# Shift_Regs.net
KiCad netlist of a schematic drawn in Altium Designer
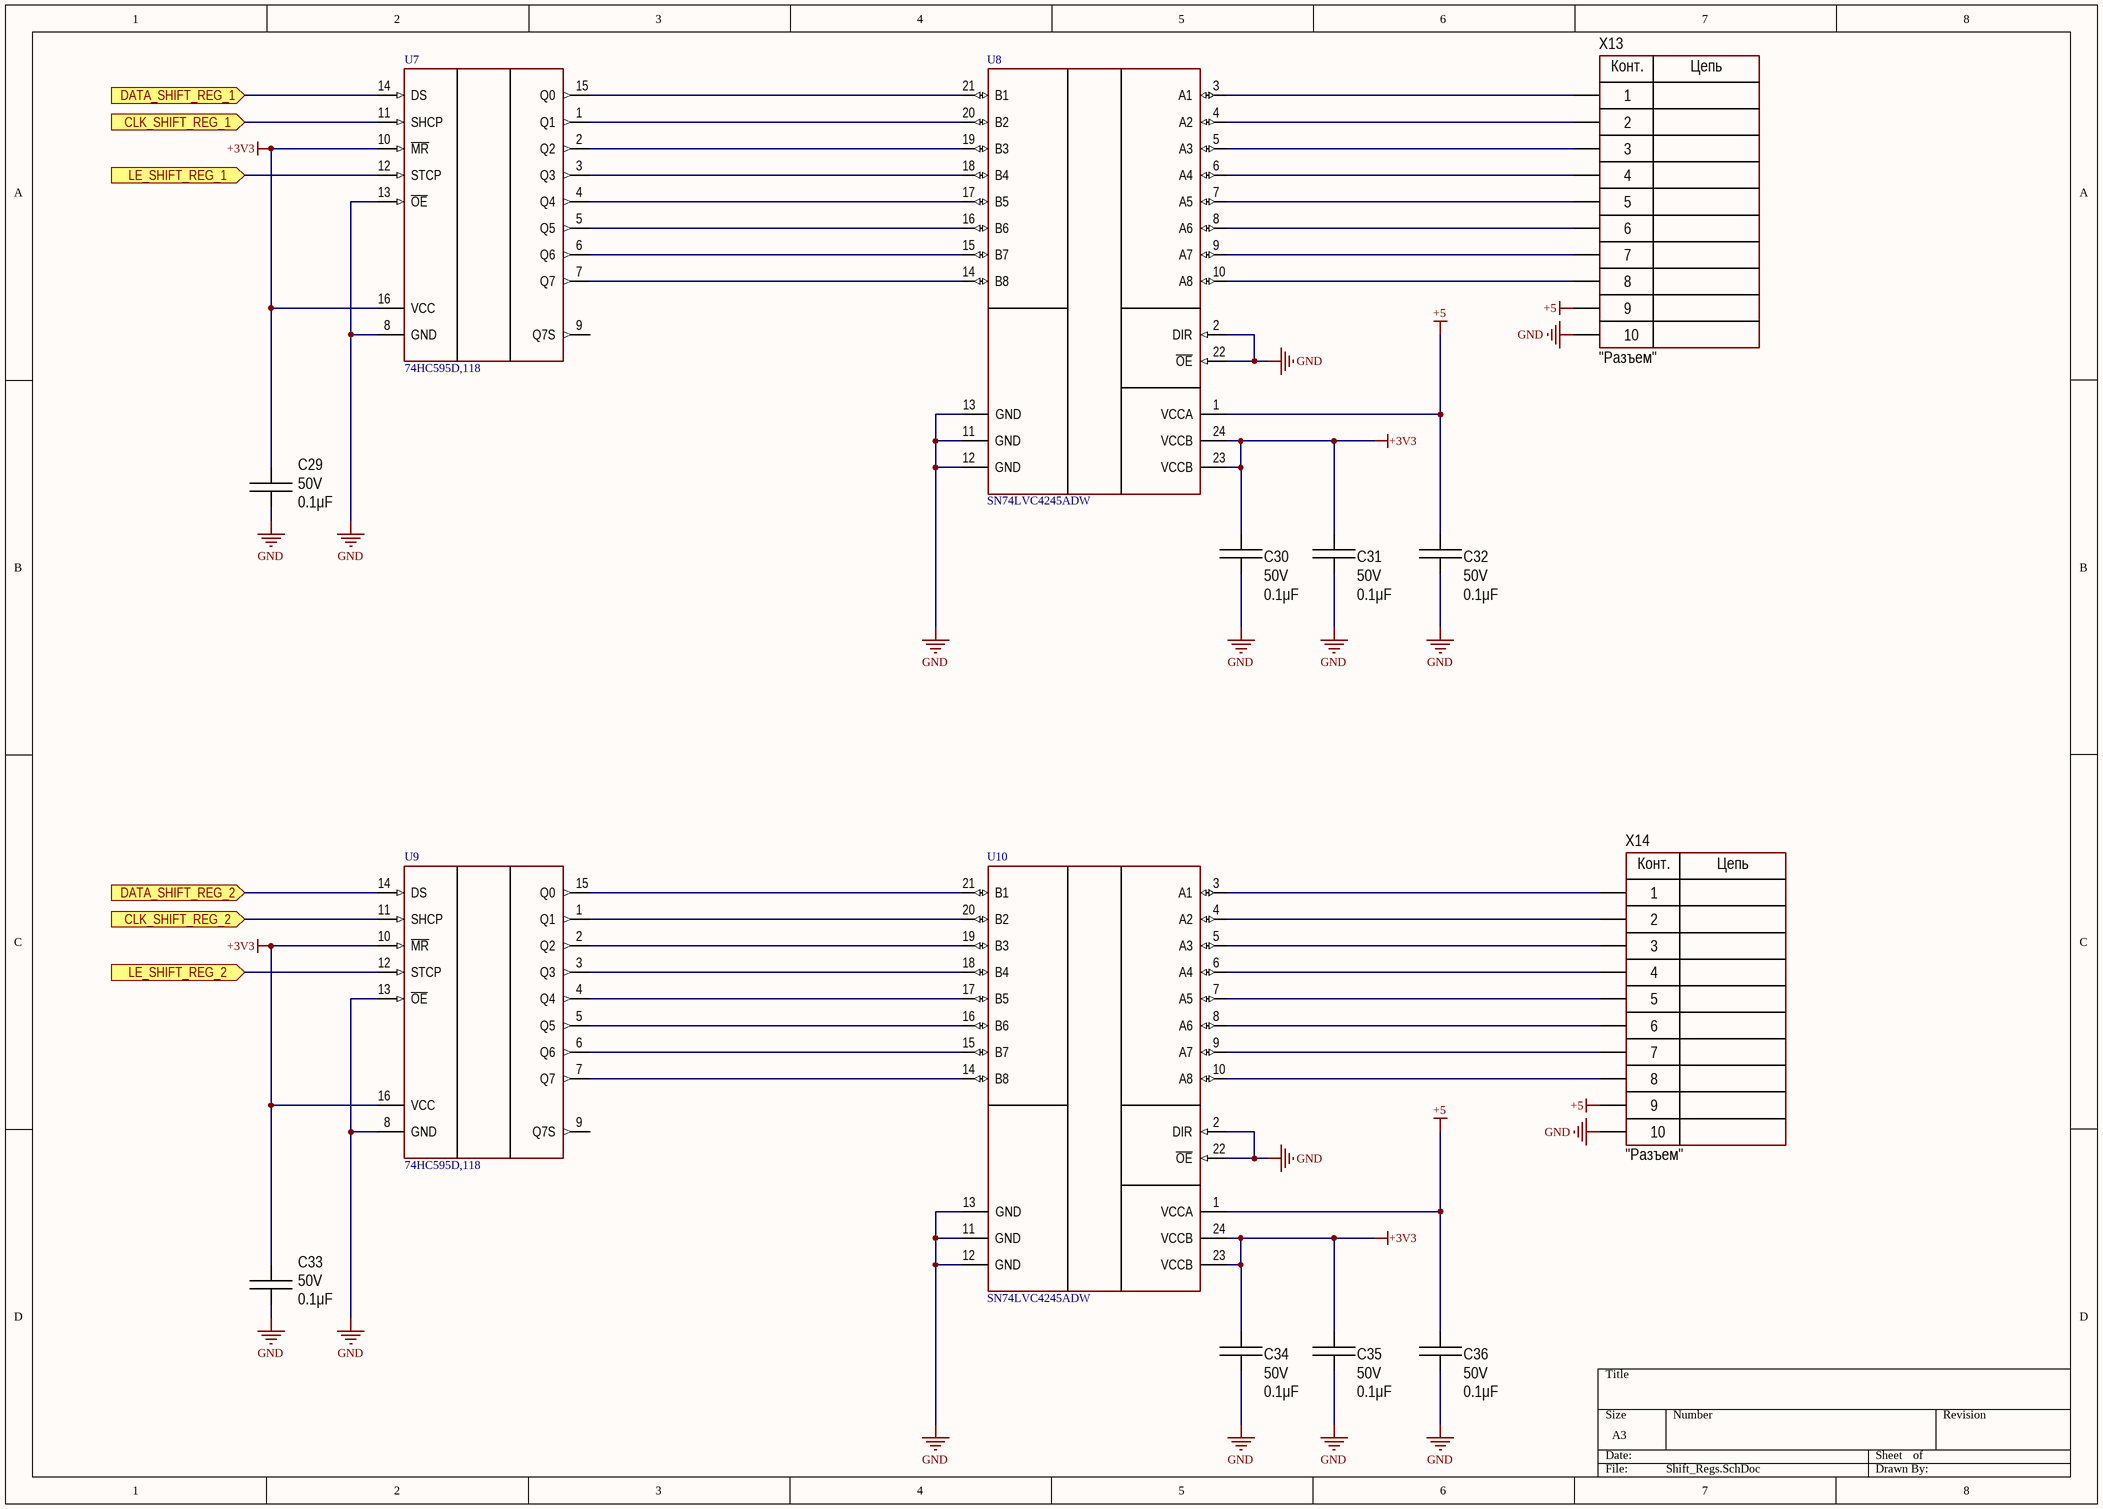
[diagram p0: Shift_Regs.SchDoc]

(export (version "E")
  (design (tool "Eeschema 10.0.6"))
  (components
    (comp (ref "C29")
      (value "0.1μF")
      (footprint "standard-case:CAP: 1206")
      (fields
        (field (name "MANUFACTURER") "Yageo")
        (field (name "PARTNUMBER") "CC1206KRX7R9BB104")
        (field (name "VALUEMANUFACTURERPARTNUMBER") "Ceramic capacitor, 0.1μF, X7R, ±10%, 50V, 1206, -55...+125°C")
        (field (name "VOLTAGE") "50V")
      )
      (libsource (lib "capacitor") (part "Ceramic_1206"))
    )
    (comp (ref "C30")
      (value "0.1μF")
      (footprint "standard-case:CAP: 1206")
      (fields
        (field (name "MANUFACTURER") "Yageo")
        (field (name "PARTNUMBER") "CC1206KRX7R9BB104")
        (field (name "VALUEMANUFACTURERPARTNUMBER") "Ceramic capacitor, 0.1μF, X7R, ±10%, 50V, 1206, -55...+125°C")
        (field (name "VOLTAGE") "50V")
      )
      (libsource (lib "capacitor") (part "Ceramic_1206"))
    )
    (comp (ref "C31")
      (value "0.1μF")
      (footprint "standard-case:CAP: 1206")
      (fields
        (field (name "MANUFACTURER") "Yageo")
        (field (name "PARTNUMBER") "CC1206KRX7R9BB104")
        (field (name "VALUEMANUFACTURERPARTNUMBER") "Ceramic capacitor, 0.1μF, X7R, ±10%, 50V, 1206, -55...+125°C")
        (field (name "VOLTAGE") "50V")
      )
      (libsource (lib "capacitor") (part "Ceramic_1206"))
    )
    (comp (ref "C32")
      (value "0.1μF")
      (footprint "standard-case:CAP: 1206")
      (fields
        (field (name "MANUFACTURER") "Yageo")
        (field (name "PARTNUMBER") "CC1206KRX7R9BB104")
        (field (name "VALUEMANUFACTURERPARTNUMBER") "Ceramic capacitor, 0.1μF, X7R, ±10%, 50V, 1206, -55...+125°C")
        (field (name "VOLTAGE") "50V")
      )
      (libsource (lib "capacitor") (part "Ceramic_1206"))
    )
    (comp (ref "C33")
      (value "0.1μF")
      (footprint "standard-case:CAP: 1206")
      (fields
        (field (name "MANUFACTURER") "Yageo")
        (field (name "PARTNUMBER") "CC1206KRX7R9BB104")
        (field (name "VALUEMANUFACTURERPARTNUMBER") "Ceramic capacitor, 0.1μF, X7R, ±10%, 50V, 1206, -55...+125°C")
        (field (name "VOLTAGE") "50V")
      )
      (libsource (lib "capacitor") (part "Ceramic_1206"))
    )
    (comp (ref "C34")
      (value "0.1μF")
      (footprint "standard-case:CAP: 1206")
      (fields
        (field (name "MANUFACTURER") "Yageo")
        (field (name "PARTNUMBER") "CC1206KRX7R9BB104")
        (field (name "VALUEMANUFACTURERPARTNUMBER") "Ceramic capacitor, 0.1μF, X7R, ±10%, 50V, 1206, -55...+125°C")
        (field (name "VOLTAGE") "50V")
      )
      (libsource (lib "capacitor") (part "Ceramic_1206"))
    )
    (comp (ref "C35")
      (value "0.1μF")
      (footprint "standard-case:CAP: 1206")
      (fields
        (field (name "MANUFACTURER") "Yageo")
        (field (name "PARTNUMBER") "CC1206KRX7R9BB104")
        (field (name "VALUEMANUFACTURERPARTNUMBER") "Ceramic capacitor, 0.1μF, X7R, ±10%, 50V, 1206, -55...+125°C")
        (field (name "VOLTAGE") "50V")
      )
      (libsource (lib "capacitor") (part "Ceramic_1206"))
    )
    (comp (ref "C36")
      (value "0.1μF")
      (footprint "standard-case:CAP: 1206")
      (fields
        (field (name "MANUFACTURER") "Yageo")
        (field (name "PARTNUMBER") "CC1206KRX7R9BB104")
        (field (name "VALUEMANUFACTURERPARTNUMBER") "Ceramic capacitor, 0.1μF, X7R, ±10%, 50V, 1206, -55...+125°C")
        (field (name "VOLTAGE") "50V")
      )
      (libsource (lib "capacitor") (part "Ceramic_1206"))
    )
    (comp (ref "U7")
      (value "74HC595D,118")
      (footprint "FP-SOT109-1-MFG")
      (description "IC SHIFT REGISTER 8BIT 16SOIC")
      (libsource (lib "74hc595d") (part "CMP-14351-000006-1"))
    )
    (comp (ref "U8")
      (value "SN74LVC4245ADW")
      (footprint "FP-DW0024A-MFG")
      (description "IC TRNSLTR BIDIRECTIONAL 24SOIC")
      (libsource (lib "SN74LVC4245ADW") (part "CMP-04899-000091-1"))
    )
    (comp (ref "U9")
      (value "74HC595D,118")
      (footprint "FP-SOT109-1-MFG")
      (description "IC SHIFT REGISTER 8BIT 16SOIC")
      (libsource (lib "74hc595d") (part "CMP-14351-000006-1"))
    )
    (comp (ref "U10")
      (value "SN74LVC4245ADW")
      (footprint "FP-DW0024A-MFG")
      (description "IC TRNSLTR BIDIRECTIONAL 24SOIC")
      (libsource (lib "SN74LVC4245ADW") (part "CMP-04899-000091-1"))
    )
    (comp (ref "X13")
      (value "~")
      (footprint "custom-case:CON: IDC-10MS")
      (fields
        (field (name "MANUFACTURER") "Connfly")
        (field (name "VALUEMANUFACTURERPARTNUMBER") "Connector, 10pin, 2.54mm, 250VAC, 3A")
        (field (name "PARTNUMBER") "IDC-10")
        (field (name "COMMENTTEXT") "\"Разъем\"")
      )
      (libsource (lib "connector") (part "IDC-10"))
    )
    (comp (ref "X14")
      (value "~")
      (footprint "custom-case:CON: IDC-10MS")
      (fields
        (field (name "MANUFACTURER") "Connfly")
        (field (name "VALUEMANUFACTURERPARTNUMBER") "Connector, 10pin, 2.54mm, 250VAC, 3A")
        (field (name "PARTNUMBER") "IDC-10")
        (field (name "COMMENTTEXT") "\"Разъем\"")
      )
      (libsource (lib "connector") (part "IDC-10"))
    )
  )
  (nets
    (net (code "1") (name "+3V3") (class "Default")
      (node (ref "C29") (pin "2") (pinfunction "2_2") (pintype "passive"))
      (node (ref "C30") (pin "2") (pinfunction "2_2") (pintype "passive"))
      (node (ref "C31") (pin "2") (pinfunction "2_2") (pintype "passive"))
      (node (ref "C33") (pin "2") (pinfunction "2_2") (pintype "passive"))
      (node (ref "C34") (pin "2") (pinfunction "2_2") (pintype "passive"))
      (node (ref "C35") (pin "2") (pinfunction "2_2") (pintype "passive"))
      (node (ref "U10") (pin "23") (pinfunction "VCCB_23") (pintype "power_in"))
      (node (ref "U10") (pin "24") (pinfunction "VCCB_24") (pintype "power_in"))
      (node (ref "U7") (pin "10") (pinfunction "~{MR}_10") (pintype "input"))
      (node (ref "U7") (pin "16") (pinfunction "VCC_16") (pintype "power_in"))
      (node (ref "U8") (pin "23") (pinfunction "VCCB_23") (pintype "power_in"))
      (node (ref "U8") (pin "24") (pinfunction "VCCB_24") (pintype "power_in"))
      (node (ref "U9") (pin "10") (pinfunction "~{MR}_10") (pintype "input"))
      (node (ref "U9") (pin "16") (pinfunction "VCC_16") (pintype "power_in"))
    )
    (net (code "2") (name "+5") (class "Default")
      (node (ref "C32") (pin "2") (pinfunction "2_2") (pintype "passive"))
      (node (ref "C36") (pin "2") (pinfunction "2_2") (pintype "passive"))
      (node (ref "U10") (pin "1") (pinfunction "VCCA_1") (pintype "power_in"))
      (node (ref "U8") (pin "1") (pinfunction "VCCA_1") (pintype "power_in"))
      (node (ref "X13") (pin "9") (pinfunction "9_9") (pintype "passive"))
      (node (ref "X14") (pin "9") (pinfunction "9_9") (pintype "passive"))
    )
    (net (code "3") (name "/CLK_SHIFT_REG_1") (class "Default")
      (node (ref "U7") (pin "11") (pinfunction "SHCP_11") (pintype "input"))
    )
    (net (code "4") (name "/CLK_SHIFT_REG_2") (class "Default")
      (node (ref "U9") (pin "11") (pinfunction "SHCP_11") (pintype "input"))
    )
    (net (code "5") (name "/DATA_SHIFT_REG_1") (class "Default")
      (node (ref "U7") (pin "14") (pinfunction "DS_14") (pintype "input"))
    )
    (net (code "6") (name "/DATA_SHIFT_REG_2") (class "Default")
      (node (ref "U9") (pin "14") (pinfunction "DS_14") (pintype "input"))
    )
    (net (code "7") (name "/LE_SHIFT_REG_1") (class "Default")
      (node (ref "U7") (pin "12") (pinfunction "STCP_12") (pintype "input"))
    )
    (net (code "8") (name "/LE_SHIFT_REG_2") (class "Default")
      (node (ref "U9") (pin "12") (pinfunction "STCP_12") (pintype "input"))
    )
    (net (code "9") (name "GND") (class "Default")
      (node (ref "C29") (pin "1") (pinfunction "1_1") (pintype "passive"))
      (node (ref "C30") (pin "1") (pinfunction "1_1") (pintype "passive"))
      (node (ref "C31") (pin "1") (pinfunction "1_1") (pintype "passive"))
      (node (ref "C32") (pin "1") (pinfunction "1_1") (pintype "passive"))
      (node (ref "C33") (pin "1") (pinfunction "1_1") (pintype "passive"))
      (node (ref "C34") (pin "1") (pinfunction "1_1") (pintype "passive"))
      (node (ref "C35") (pin "1") (pinfunction "1_1") (pintype "passive"))
      (node (ref "C36") (pin "1") (pinfunction "1_1") (pintype "passive"))
      (node (ref "U10") (pin "11") (pinfunction "GND_11") (pintype "power_in"))
      (node (ref "U10") (pin "12") (pinfunction "GND_12") (pintype "power_in"))
      (node (ref "U10") (pin "13") (pinfunction "GND_13") (pintype "power_in"))
      (node (ref "U10") (pin "2") (pinfunction "DIR_2") (pintype "input"))
      (node (ref "U10") (pin "22") (pinfunction "~{OE}_22") (pintype "input"))
      (node (ref "U7") (pin "13") (pinfunction "~{OE}_13") (pintype "input"))
      (node (ref "U7") (pin "8") (pinfunction "GND_8") (pintype "power_in"))
      (node (ref "U8") (pin "11") (pinfunction "GND_11") (pintype "power_in"))
      (node (ref "U8") (pin "12") (pinfunction "GND_12") (pintype "power_in"))
      (node (ref "U8") (pin "13") (pinfunction "GND_13") (pintype "power_in"))
      (node (ref "U8") (pin "2") (pinfunction "DIR_2") (pintype "input"))
      (node (ref "U8") (pin "22") (pinfunction "~{OE}_22") (pintype "input"))
      (node (ref "U9") (pin "13") (pinfunction "~{OE}_13") (pintype "input"))
      (node (ref "U9") (pin "8") (pinfunction "GND_8") (pintype "power_in"))
      (node (ref "X13") (pin "10") (pinfunction "10_10") (pintype "passive"))
      (node (ref "X14") (pin "10") (pinfunction "10_10") (pintype "passive"))
    )
    (net (code "10") (name "Net-(U7-Q0)") (class "Default")
      (node (ref "U7") (pin "15") (pinfunction "Q0_15") (pintype "output"))
      (node (ref "U8") (pin "21") (pinfunction "B1_21") (pintype "bidirectional"))
    )
    (net (code "11") (name "Net-(U7-Q1)") (class "Default")
      (node (ref "U7") (pin "1") (pinfunction "Q1_1") (pintype "output"))
      (node (ref "U8") (pin "20") (pinfunction "B2_20") (pintype "bidirectional"))
    )
    (net (code "12") (name "Net-(U7-Q2)") (class "Default")
      (node (ref "U7") (pin "2") (pinfunction "Q2_2") (pintype "output"))
      (node (ref "U8") (pin "19") (pinfunction "B3_19") (pintype "bidirectional"))
    )
    (net (code "13") (name "Net-(U7-Q3)") (class "Default")
      (node (ref "U7") (pin "3") (pinfunction "Q3_3") (pintype "output"))
      (node (ref "U8") (pin "18") (pinfunction "B4_18") (pintype "bidirectional"))
    )
    (net (code "14") (name "Net-(U7-Q4)") (class "Default")
      (node (ref "U7") (pin "4") (pinfunction "Q4_4") (pintype "output"))
      (node (ref "U8") (pin "17") (pinfunction "B5_17") (pintype "bidirectional"))
    )
    (net (code "15") (name "Net-(U7-Q5)") (class "Default")
      (node (ref "U7") (pin "5") (pinfunction "Q5_5") (pintype "output"))
      (node (ref "U8") (pin "16") (pinfunction "B6_16") (pintype "bidirectional"))
    )
    (net (code "16") (name "Net-(U7-Q6)") (class "Default")
      (node (ref "U7") (pin "6") (pinfunction "Q6_6") (pintype "output"))
      (node (ref "U8") (pin "15") (pinfunction "B7_15") (pintype "bidirectional"))
    )
    (net (code "17") (name "Net-(U7-Q7)") (class "Default")
      (node (ref "U7") (pin "7") (pinfunction "Q7_7") (pintype "output"))
      (node (ref "U8") (pin "14") (pinfunction "B8_14") (pintype "bidirectional"))
    )
    (net (code "18") (name "Net-(U8-A1)") (class "Default")
      (node (ref "U8") (pin "3") (pinfunction "A1_3") (pintype "bidirectional"))
      (node (ref "X13") (pin "1") (pinfunction "1_1") (pintype "passive"))
    )
    (net (code "19") (name "Net-(U8-A2)") (class "Default")
      (node (ref "U8") (pin "4") (pinfunction "A2_4") (pintype "bidirectional"))
      (node (ref "X13") (pin "2") (pinfunction "2_2") (pintype "passive"))
    )
    (net (code "20") (name "Net-(U8-A3)") (class "Default")
      (node (ref "U8") (pin "5") (pinfunction "A3_5") (pintype "bidirectional"))
      (node (ref "X13") (pin "3") (pinfunction "3_3") (pintype "passive"))
    )
    (net (code "21") (name "Net-(U8-A4)") (class "Default")
      (node (ref "U8") (pin "6") (pinfunction "A4_6") (pintype "bidirectional"))
      (node (ref "X13") (pin "4") (pinfunction "4_4") (pintype "passive"))
    )
    (net (code "22") (name "Net-(U8-A5)") (class "Default")
      (node (ref "U8") (pin "7") (pinfunction "A5_7") (pintype "bidirectional"))
      (node (ref "X13") (pin "5") (pinfunction "5_5") (pintype "passive"))
    )
    (net (code "23") (name "Net-(U8-A6)") (class "Default")
      (node (ref "U8") (pin "8") (pinfunction "A6_8") (pintype "bidirectional"))
      (node (ref "X13") (pin "6") (pinfunction "6_6") (pintype "passive"))
    )
    (net (code "24") (name "Net-(U8-A7)") (class "Default")
      (node (ref "U8") (pin "9") (pinfunction "A7_9") (pintype "bidirectional"))
      (node (ref "X13") (pin "7") (pinfunction "7_7") (pintype "passive"))
    )
    (net (code "25") (name "Net-(U8-A8)") (class "Default")
      (node (ref "U8") (pin "10") (pinfunction "A8_10") (pintype "bidirectional"))
      (node (ref "X13") (pin "8") (pinfunction "8_8") (pintype "passive"))
    )
    (net (code "26") (name "Net-(U10-A1)") (class "Default")
      (node (ref "U10") (pin "3") (pinfunction "A1_3") (pintype "bidirectional"))
      (node (ref "X14") (pin "1") (pinfunction "1_1") (pintype "passive"))
    )
    (net (code "27") (name "Net-(U10-A2)") (class "Default")
      (node (ref "U10") (pin "4") (pinfunction "A2_4") (pintype "bidirectional"))
      (node (ref "X14") (pin "2") (pinfunction "2_2") (pintype "passive"))
    )
    (net (code "28") (name "Net-(U10-A3)") (class "Default")
      (node (ref "U10") (pin "5") (pinfunction "A3_5") (pintype "bidirectional"))
      (node (ref "X14") (pin "3") (pinfunction "3_3") (pintype "passive"))
    )
    (net (code "29") (name "Net-(U10-A4)") (class "Default")
      (node (ref "U10") (pin "6") (pinfunction "A4_6") (pintype "bidirectional"))
      (node (ref "X14") (pin "4") (pinfunction "4_4") (pintype "passive"))
    )
    (net (code "30") (name "Net-(U10-A5)") (class "Default")
      (node (ref "U10") (pin "7") (pinfunction "A5_7") (pintype "bidirectional"))
      (node (ref "X14") (pin "5") (pinfunction "5_5") (pintype "passive"))
    )
    (net (code "31") (name "Net-(U10-A6)") (class "Default")
      (node (ref "U10") (pin "8") (pinfunction "A6_8") (pintype "bidirectional"))
      (node (ref "X14") (pin "6") (pinfunction "6_6") (pintype "passive"))
    )
    (net (code "32") (name "Net-(U10-A7)") (class "Default")
      (node (ref "U10") (pin "9") (pinfunction "A7_9") (pintype "bidirectional"))
      (node (ref "X14") (pin "7") (pinfunction "7_7") (pintype "passive"))
    )
    (net (code "33") (name "Net-(U10-A8)") (class "Default")
      (node (ref "U10") (pin "10") (pinfunction "A8_10") (pintype "bidirectional"))
      (node (ref "X14") (pin "8") (pinfunction "8_8") (pintype "passive"))
    )
    (net (code "34") (name "Net-(U10-B1)") (class "Default")
      (node (ref "U10") (pin "21") (pinfunction "B1_21") (pintype "bidirectional"))
      (node (ref "U9") (pin "15") (pinfunction "Q0_15") (pintype "output"))
    )
    (net (code "35") (name "Net-(U10-B2)") (class "Default")
      (node (ref "U10") (pin "20") (pinfunction "B2_20") (pintype "bidirectional"))
      (node (ref "U9") (pin "1") (pinfunction "Q1_1") (pintype "output"))
    )
    (net (code "36") (name "Net-(U10-B3)") (class "Default")
      (node (ref "U10") (pin "19") (pinfunction "B3_19") (pintype "bidirectional"))
      (node (ref "U9") (pin "2") (pinfunction "Q2_2") (pintype "output"))
    )
    (net (code "37") (name "Net-(U10-B4)") (class "Default")
      (node (ref "U10") (pin "18") (pinfunction "B4_18") (pintype "bidirectional"))
      (node (ref "U9") (pin "3") (pinfunction "Q3_3") (pintype "output"))
    )
    (net (code "38") (name "Net-(U10-B5)") (class "Default")
      (node (ref "U10") (pin "17") (pinfunction "B5_17") (pintype "bidirectional"))
      (node (ref "U9") (pin "4") (pinfunction "Q4_4") (pintype "output"))
    )
    (net (code "39") (name "Net-(U10-B6)") (class "Default")
      (node (ref "U10") (pin "16") (pinfunction "B6_16") (pintype "bidirectional"))
      (node (ref "U9") (pin "5") (pinfunction "Q5_5") (pintype "output"))
    )
    (net (code "40") (name "Net-(U10-B7)") (class "Default")
      (node (ref "U10") (pin "15") (pinfunction "B7_15") (pintype "bidirectional"))
      (node (ref "U9") (pin "6") (pinfunction "Q6_6") (pintype "output"))
    )
    (net (code "41") (name "Net-(U10-B8)") (class "Default")
      (node (ref "U10") (pin "14") (pinfunction "B8_14") (pintype "bidirectional"))
      (node (ref "U9") (pin "7") (pinfunction "Q7_7") (pintype "output"))
    )
    (net (code "42") (name "unconnected-(U7-Q7S-Pad9)") (class "Default")
      (node (ref "U7") (pin "9") (pinfunction "Q7S_9") (pintype "output"))
    )
    (net (code "43") (name "unconnected-(U9-Q7S-Pad9)") (class "Default")
      (node (ref "U9") (pin "9") (pinfunction "Q7S_9") (pintype "output"))
    )
  )
)
